# LEDclock_DCF77-RTC-BAT_ProPrj_2026-05-02.net
KiCad netlist of a schematic drawn in EasyEDA Pro
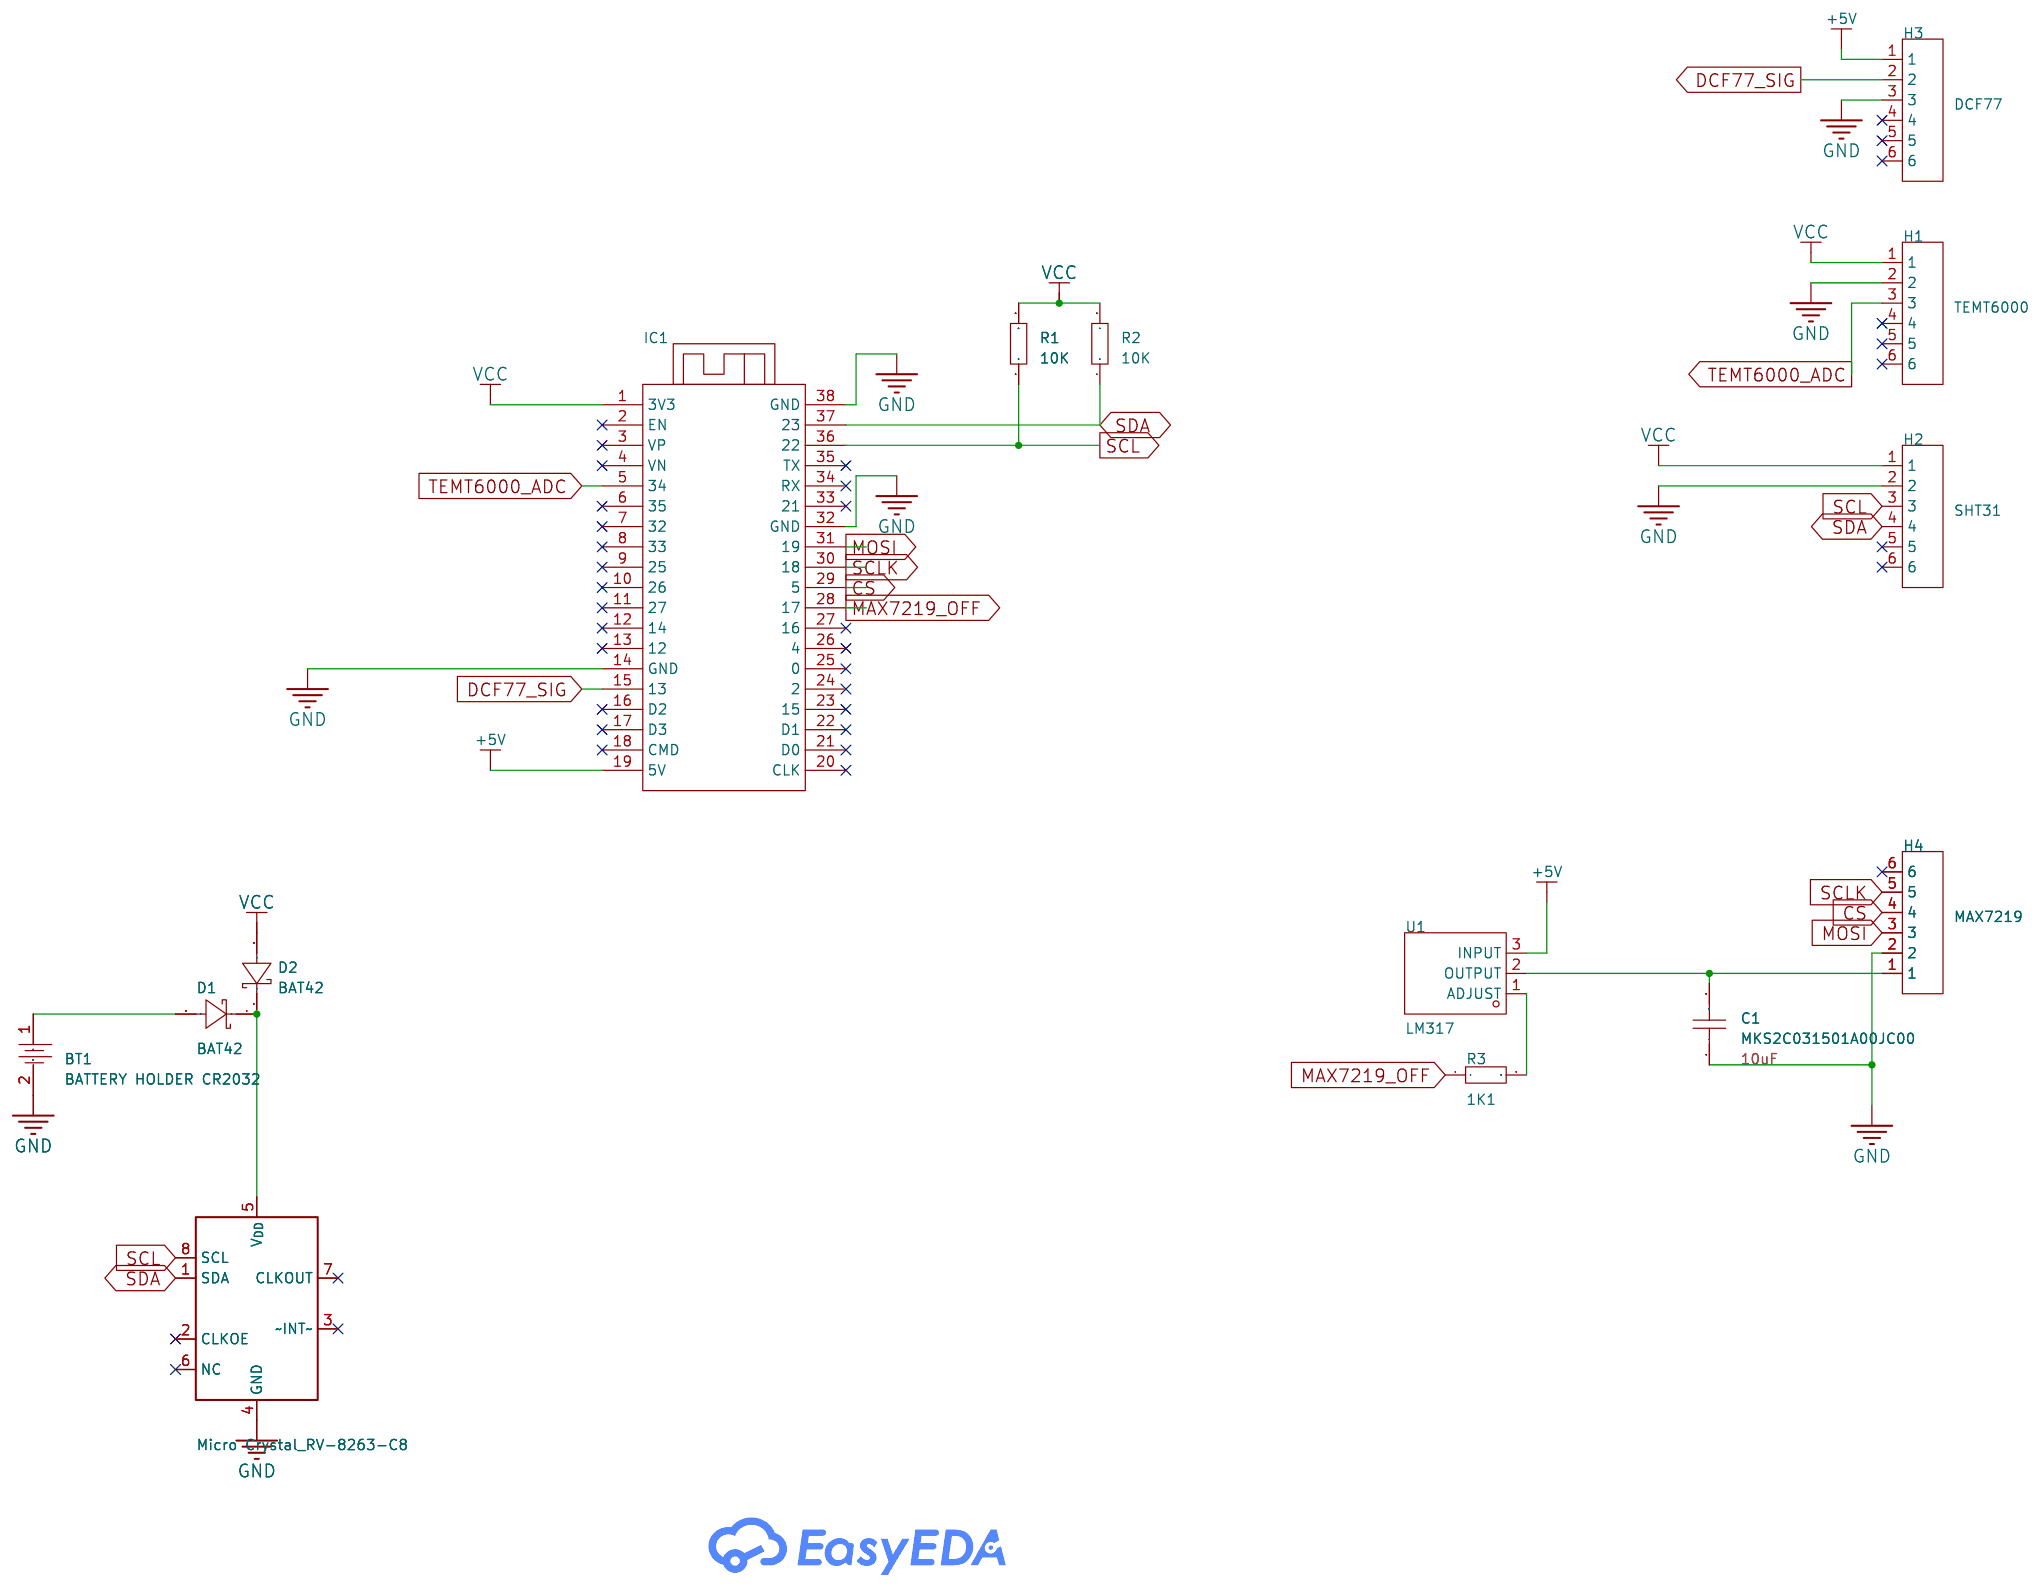
[diagram p0: schematic sheet]

(export (version "E")
  (design (tool "Eeschema 10.0.6"))
  (components
    (comp (ref "BT1")
      (value "BATTERY HOLDER CR2032")
      (footprint "easyedapro:BAT-TH_FBA25014-S02B2004K")
      (fields
        (field (name "Manufacturer Part") "FBA25014-S02B2004K")
        (field (name "Manufacturer") "TXGA(特思嘉)")
      )
      (libsource (lib "easyedapro") (part "FBA25014-S02B2004K"))
    )
    (comp (ref "C1")
      (value "MKS2C031501A00JC00")
      (footprint "easyedapro:CAP-TH_L7.2-W2.5-P5.00-D0.5-1")
      (fields (field (name "Manufacturer") "WIMA") (field (name "Capacitance") "10uF"))
      (libsource (lib "easyedapro") (part "MKS2C031501A00JC00"))
    )
    (comp (ref "D1")
      (value "BAT42")
      (footprint "easyedapro:DO-35_BD1.8-L4.1-P7.00-D0.5-RD")
      (fields (field (name "Manufacturer") "ST(意法半导体)"))
      (libsource (lib "easyedapro") (part "BAT42"))
    )
    (comp (ref "D2")
      (value "BAT42")
      (footprint "easyedapro:DO-35_BD1.8-L4.1-P7.00-D0.5-RD")
      (fields (field (name "Manufacturer") "ST(意法半导体)"))
      (libsource (lib "easyedapro") (part "BAT42"))
    )
    (comp (ref "H1")
      (value "TEMT6000")
      (footprint "easyedapro:CONN-TH_SSQ-106-03-G-S")
      (fields (field (name "Manufacturer") "SAMTEC"))
      (libsource (lib "easyedapro") (part "SSQ-106-03-G-S"))
    )
    (comp (ref "H2")
      (value "SHT31")
      (footprint "easyedapro:CONN-TH_SSQ-106-03-G-S")
      (fields (field (name "Manufacturer") "SAMTEC"))
      (libsource (lib "easyedapro") (part "SSQ-106-03-G-S"))
    )
    (comp (ref "H3")
      (value "DCF77")
      (footprint "easyedapro:CONN-TH_SSQ-106-03-G-S")
      (fields (field (name "Manufacturer") "SAMTEC"))
      (libsource (lib "easyedapro") (part "SSQ-106-03-G-S"))
    )
    (comp (ref "H4")
      (value "MAX7219")
      (footprint "easyedapro:CONN-TH_SSQ-106-03-G-S")
      (fields (field (name "Manufacturer") "SAMTEC"))
      (libsource (lib "easyedapro") (part "SSQ-106-03-G-S"))
    )
    (comp (ref "IC1")
      (value "~")
      (footprint "easyedapro:ESP32 WROOM devkit")
      (libsource (lib "easyedapro") (part "ESP32 WROOM defkit"))
    )
    (comp (ref "IC2")
      (value "RV-8263-C8")
      (footprint "easyedapro:Micro Crystal:RV-8263-C8")
      (libsource (lib "easyedapro") (part "Micro Crystal_RV-8263-C8"))
    )
    (comp (ref "R1") (value "10K") (footprint "easyedapro:R0603") (libsource (lib "easyedapro") (part "Res")))
    (comp (ref "R2") (value "10K") (footprint "easyedapro:R0603") (libsource (lib "easyedapro") (part "Res")))
    (comp (ref "R3") (value "1K1") (footprint "easyedapro:R0603") (libsource (lib "easyedapro") (part "Res")))
    (comp (ref "U1")
      (value "LM317")
      (footprint "easyedapro:TO-220-3_L9.9-W4.5-P2.54-L-1")
      (fields (field (name "Manufacturer") "IDCHIP(英锐芯)"))
      (libsource (lib "easyedapro") (part "LM317_C7463411"))
    )
  )
  (nets
    (net (code "1") (name "+5V") (class "Default")
      (node (ref "H3") (pin "1") (pinfunction "1_1") (pintype "unspecified"))
      (node (ref "IC1") (pin "19") (pinfunction "5V_19") (pintype "input"))
      (node (ref "U1") (pin "3") (pinfunction "INPUT_3") (pintype "unspecified"))
    )
    (net (code "2") (name "CS") (class "Default")
      (node (ref "H4") (pin "4") (pinfunction "4_4") (pintype "unspecified"))
      (node (ref "IC1") (pin "29") (pinfunction "5_29") (pintype "input"))
    )
    (net (code "3") (name "DCF77_SIG") (class "Default")
      (node (ref "H3") (pin "2") (pinfunction "2_2") (pintype "unspecified"))
      (node (ref "IC1") (pin "15") (pinfunction "13_15") (pintype "input"))
    )
    (net (code "4") (name "GND") (class "Default")
      (node (ref "BT1") (pin "2") (pinfunction "2_2") (pintype "input"))
      (node (ref "C1") (pin "1") (pinfunction "1_1") (pintype "unspecified"))
      (node (ref "H1") (pin "2") (pinfunction "2_2") (pintype "unspecified"))
      (node (ref "H2") (pin "2") (pinfunction "2_2") (pintype "unspecified"))
      (node (ref "H3") (pin "3") (pinfunction "3_3") (pintype "unspecified"))
      (node (ref "H4") (pin "2") (pinfunction "2_2") (pintype "unspecified"))
      (node (ref "IC1") (pin "14") (pinfunction "GND_14") (pintype "input"))
      (node (ref "IC1") (pin "32") (pinfunction "GND_32") (pintype "input"))
      (node (ref "IC1") (pin "38") (pinfunction "GND_38") (pintype "input"))
      (node (ref "IC2") (pin "4") (pinfunction "GND_4") (pintype "unspecified"))
    )
    (net (code "5") (name "MAX7219_OFF") (class "Default")
      (node (ref "IC1") (pin "28") (pinfunction "17_28") (pintype "input"))
      (node (ref "R3") (pin "1") (pinfunction "1_1") (pintype "input"))
    )
    (net (code "6") (name "MOSI") (class "Default")
      (node (ref "H4") (pin "3") (pinfunction "3_3") (pintype "unspecified"))
      (node (ref "IC1") (pin "31") (pinfunction "19_31") (pintype "input"))
    )
    (net (code "7") (name "Net-(D1-A)") (class "Default")
      (node (ref "BT1") (pin "1") (pinfunction "1_1") (pintype "input"))
      (node (ref "D1") (pin "2") (pinfunction "A_2") (pintype "unspecified"))
    )
    (net (code "8") (name "Net-(D1-K)") (class "Default")
      (node (ref "D1") (pin "1") (pinfunction "K_1") (pintype "unspecified"))
      (node (ref "D2") (pin "1") (pinfunction "K_1") (pintype "unspecified"))
      (node (ref "IC2") (pin "5") (pinfunction "V_{DD}_5") (pintype "unspecified"))
    )
    (net (code "9") (name "Net-(U1-ADJUST)") (class "Default")
      (node (ref "R3") (pin "2") (pinfunction "2_2") (pintype "input"))
      (node (ref "U1") (pin "1") (pinfunction "ADJUST_1") (pintype "unspecified"))
    )
    (net (code "10") (name "Net-(U1-OUTPUT)") (class "Default")
      (node (ref "C1") (pin "2") (pinfunction "2_2") (pintype "unspecified"))
      (node (ref "H4") (pin "1") (pinfunction "1_1") (pintype "unspecified"))
      (node (ref "U1") (pin "2") (pinfunction "OUTPUT_2") (pintype "unspecified"))
    )
    (net (code "11") (name "SCL") (class "Default")
      (node (ref "H2") (pin "3") (pinfunction "3_3") (pintype "unspecified"))
      (node (ref "IC1") (pin "36") (pinfunction "22_36") (pintype "input"))
      (node (ref "IC2") (pin "8") (pinfunction "SCL_8") (pintype "input"))
      (node (ref "R1") (pin "1") (pinfunction "1_1") (pintype "input"))
    )
    (net (code "12") (name "SCLK") (class "Default")
      (node (ref "H4") (pin "5") (pinfunction "5_5") (pintype "unspecified"))
      (node (ref "IC1") (pin "30") (pinfunction "18_30") (pintype "input"))
    )
    (net (code "13") (name "SDA") (class "Default")
      (node (ref "H2") (pin "4") (pinfunction "4_4") (pintype "unspecified"))
      (node (ref "IC1") (pin "37") (pinfunction "23_37") (pintype "input"))
      (node (ref "IC2") (pin "1") (pinfunction "SDA_1") (pintype "bidirectional"))
      (node (ref "R2") (pin "1") (pinfunction "1_1") (pintype "input"))
    )
    (net (code "14") (name "TEMT6000_ADC") (class "Default")
      (node (ref "H1") (pin "3") (pinfunction "3_3") (pintype "unspecified"))
      (node (ref "IC1") (pin "5") (pinfunction "34_5") (pintype "input"))
    )
    (net (code "15") (name "VCC") (class "Default")
      (node (ref "D2") (pin "2") (pinfunction "A_2") (pintype "unspecified"))
      (node (ref "H1") (pin "1") (pinfunction "1_1") (pintype "unspecified"))
      (node (ref "H2") (pin "1") (pinfunction "1_1") (pintype "unspecified"))
      (node (ref "IC1") (pin "1") (pinfunction "3V3_1") (pintype "input"))
      (node (ref "R1") (pin "2") (pinfunction "2_2") (pintype "input"))
      (node (ref "R2") (pin "2") (pinfunction "2_2") (pintype "input"))
    )
    (net (code "16") (name "unconnected-(H1-Pad4)") (class "Default")
      (node (ref "H1") (pin "4") (pinfunction "4_4") (pintype "unspecified+no_connect"))
    )
    (net (code "17") (name "unconnected-(H1-Pad5)") (class "Default")
      (node (ref "H1") (pin "5") (pinfunction "5_5") (pintype "unspecified+no_connect"))
    )
    (net (code "18") (name "unconnected-(H1-Pad6)") (class "Default")
      (node (ref "H1") (pin "6") (pinfunction "6_6") (pintype "unspecified+no_connect"))
    )
    (net (code "19") (name "unconnected-(H2-Pad5)") (class "Default")
      (node (ref "H2") (pin "5") (pinfunction "5_5") (pintype "unspecified+no_connect"))
    )
    (net (code "20") (name "unconnected-(H2-Pad6)") (class "Default")
      (node (ref "H2") (pin "6") (pinfunction "6_6") (pintype "unspecified+no_connect"))
    )
    (net (code "21") (name "unconnected-(H3-Pad4)") (class "Default")
      (node (ref "H3") (pin "4") (pinfunction "4_4") (pintype "unspecified+no_connect"))
    )
    (net (code "22") (name "unconnected-(H3-Pad5)") (class "Default")
      (node (ref "H3") (pin "5") (pinfunction "5_5") (pintype "unspecified+no_connect"))
    )
    (net (code "23") (name "unconnected-(H3-Pad6)") (class "Default")
      (node (ref "H3") (pin "6") (pinfunction "6_6") (pintype "unspecified+no_connect"))
    )
    (net (code "24") (name "unconnected-(H4-Pad6)") (class "Default")
      (node (ref "H4") (pin "6") (pinfunction "6_6") (pintype "unspecified+no_connect"))
    )
    (net (code "25") (name "unconnected-(IC1-0-Pad25)") (class "Default")
      (node (ref "IC1") (pin "25") (pinfunction "0_25") (pintype "input+no_connect"))
    )
    (net (code "26") (name "unconnected-(IC1-2-Pad24)") (class "Default")
      (node (ref "IC1") (pin "24") (pinfunction "2_24") (pintype "input+no_connect"))
    )
    (net (code "27") (name "unconnected-(IC1-4-Pad26)") (class "Default")
      (node (ref "IC1") (pin "26") (pinfunction "4_26") (pintype "input+no_connect"))
    )
    (net (code "28") (name "unconnected-(IC1-12-Pad13)") (class "Default")
      (node (ref "IC1") (pin "13") (pinfunction "12_13") (pintype "input+no_connect"))
    )
    (net (code "29") (name "unconnected-(IC1-14-Pad12)") (class "Default")
      (node (ref "IC1") (pin "12") (pinfunction "14_12") (pintype "input+no_connect"))
    )
    (net (code "30") (name "unconnected-(IC1-15-Pad23)") (class "Default")
      (node (ref "IC1") (pin "23") (pinfunction "15_23") (pintype "input+no_connect"))
    )
    (net (code "31") (name "unconnected-(IC1-16-Pad27)") (class "Default")
      (node (ref "IC1") (pin "27") (pinfunction "16_27") (pintype "input+no_connect"))
    )
    (net (code "32") (name "unconnected-(IC1-21-Pad33)") (class "Default")
      (node (ref "IC1") (pin "33") (pinfunction "21_33") (pintype "input+no_connect"))
    )
    (net (code "33") (name "unconnected-(IC1-25-Pad9)") (class "Default")
      (node (ref "IC1") (pin "9") (pinfunction "25_9") (pintype "input+no_connect"))
    )
    (net (code "34") (name "unconnected-(IC1-26-Pad10)") (class "Default")
      (node (ref "IC1") (pin "10") (pinfunction "26_10") (pintype "input+no_connect"))
    )
    (net (code "35") (name "unconnected-(IC1-27-Pad11)") (class "Default")
      (node (ref "IC1") (pin "11") (pinfunction "27_11") (pintype "input+no_connect"))
    )
    (net (code "36") (name "unconnected-(IC1-32-Pad7)") (class "Default")
      (node (ref "IC1") (pin "7") (pinfunction "32_7") (pintype "input+no_connect"))
    )
    (net (code "37") (name "unconnected-(IC1-33-Pad8)") (class "Default")
      (node (ref "IC1") (pin "8") (pinfunction "33_8") (pintype "input+no_connect"))
    )
    (net (code "38") (name "unconnected-(IC1-35-Pad6)") (class "Default")
      (node (ref "IC1") (pin "6") (pinfunction "35_6") (pintype "input+no_connect"))
    )
    (net (code "39") (name "unconnected-(IC1-CLK-Pad20)") (class "Default")
      (node (ref "IC1") (pin "20") (pinfunction "CLK_20") (pintype "input+no_connect"))
    )
    (net (code "40") (name "unconnected-(IC1-CMD-Pad18)") (class "Default")
      (node (ref "IC1") (pin "18") (pinfunction "CMD_18") (pintype "input+no_connect"))
    )
    (net (code "41") (name "unconnected-(IC1-D0-Pad21)") (class "Default")
      (node (ref "IC1") (pin "21") (pinfunction "D0_21") (pintype "input+no_connect"))
    )
    (net (code "42") (name "unconnected-(IC1-D1-Pad22)") (class "Default")
      (node (ref "IC1") (pin "22") (pinfunction "D1_22") (pintype "input+no_connect"))
    )
    (net (code "43") (name "unconnected-(IC1-D2-Pad16)") (class "Default")
      (node (ref "IC1") (pin "16") (pinfunction "D2_16") (pintype "input+no_connect"))
    )
    (net (code "44") (name "unconnected-(IC1-D3-Pad17)") (class "Default")
      (node (ref "IC1") (pin "17") (pinfunction "D3_17") (pintype "input+no_connect"))
    )
    (net (code "45") (name "unconnected-(IC1-EN-Pad2)") (class "Default")
      (node (ref "IC1") (pin "2") (pinfunction "EN_2") (pintype "input+no_connect"))
    )
    (net (code "46") (name "unconnected-(IC1-RX-Pad34)") (class "Default")
      (node (ref "IC1") (pin "34") (pinfunction "RX_34") (pintype "input+no_connect"))
    )
    (net (code "47") (name "unconnected-(IC1-TX-Pad35)") (class "Default")
      (node (ref "IC1") (pin "35") (pinfunction "TX_35") (pintype "input+no_connect"))
    )
    (net (code "48") (name "unconnected-(IC1-VN-Pad4)") (class "Default")
      (node (ref "IC1") (pin "4") (pinfunction "VN_4") (pintype "input+no_connect"))
    )
    (net (code "49") (name "unconnected-(IC1-VP-Pad3)") (class "Default")
      (node (ref "IC1") (pin "3") (pinfunction "VP_3") (pintype "input+no_connect"))
    )
    (net (code "50") (name "unconnected-(IC2-CLKOE-Pad2)") (class "Default")
      (node (ref "IC2") (pin "2") (pinfunction "CLKOE_2") (pintype "input+no_connect"))
    )
    (net (code "51") (name "unconnected-(IC2-CLKOUT-Pad7)") (class "Default")
      (node (ref "IC2") (pin "7") (pinfunction "CLKOUT_7") (pintype "output+no_connect"))
    )
    (net (code "52") (name "unconnected-(IC2-NC-Pad6)") (class "Default")
      (node (ref "IC2") (pin "6") (pinfunction "NC_6") (pintype "unspecified+no_connect"))
    )
    (net (code "53") (name "unconnected-(IC2-~INT~-Pad3)") (class "Default")
      (node (ref "IC2") (pin "3") (pinfunction "~INT~_3") (pintype "output+no_connect"))
    )
  )
)
